# HVDCS_S3A6_48_TQFP_v1p00.net
KiCad netlist of a schematic drawn in EAGLE
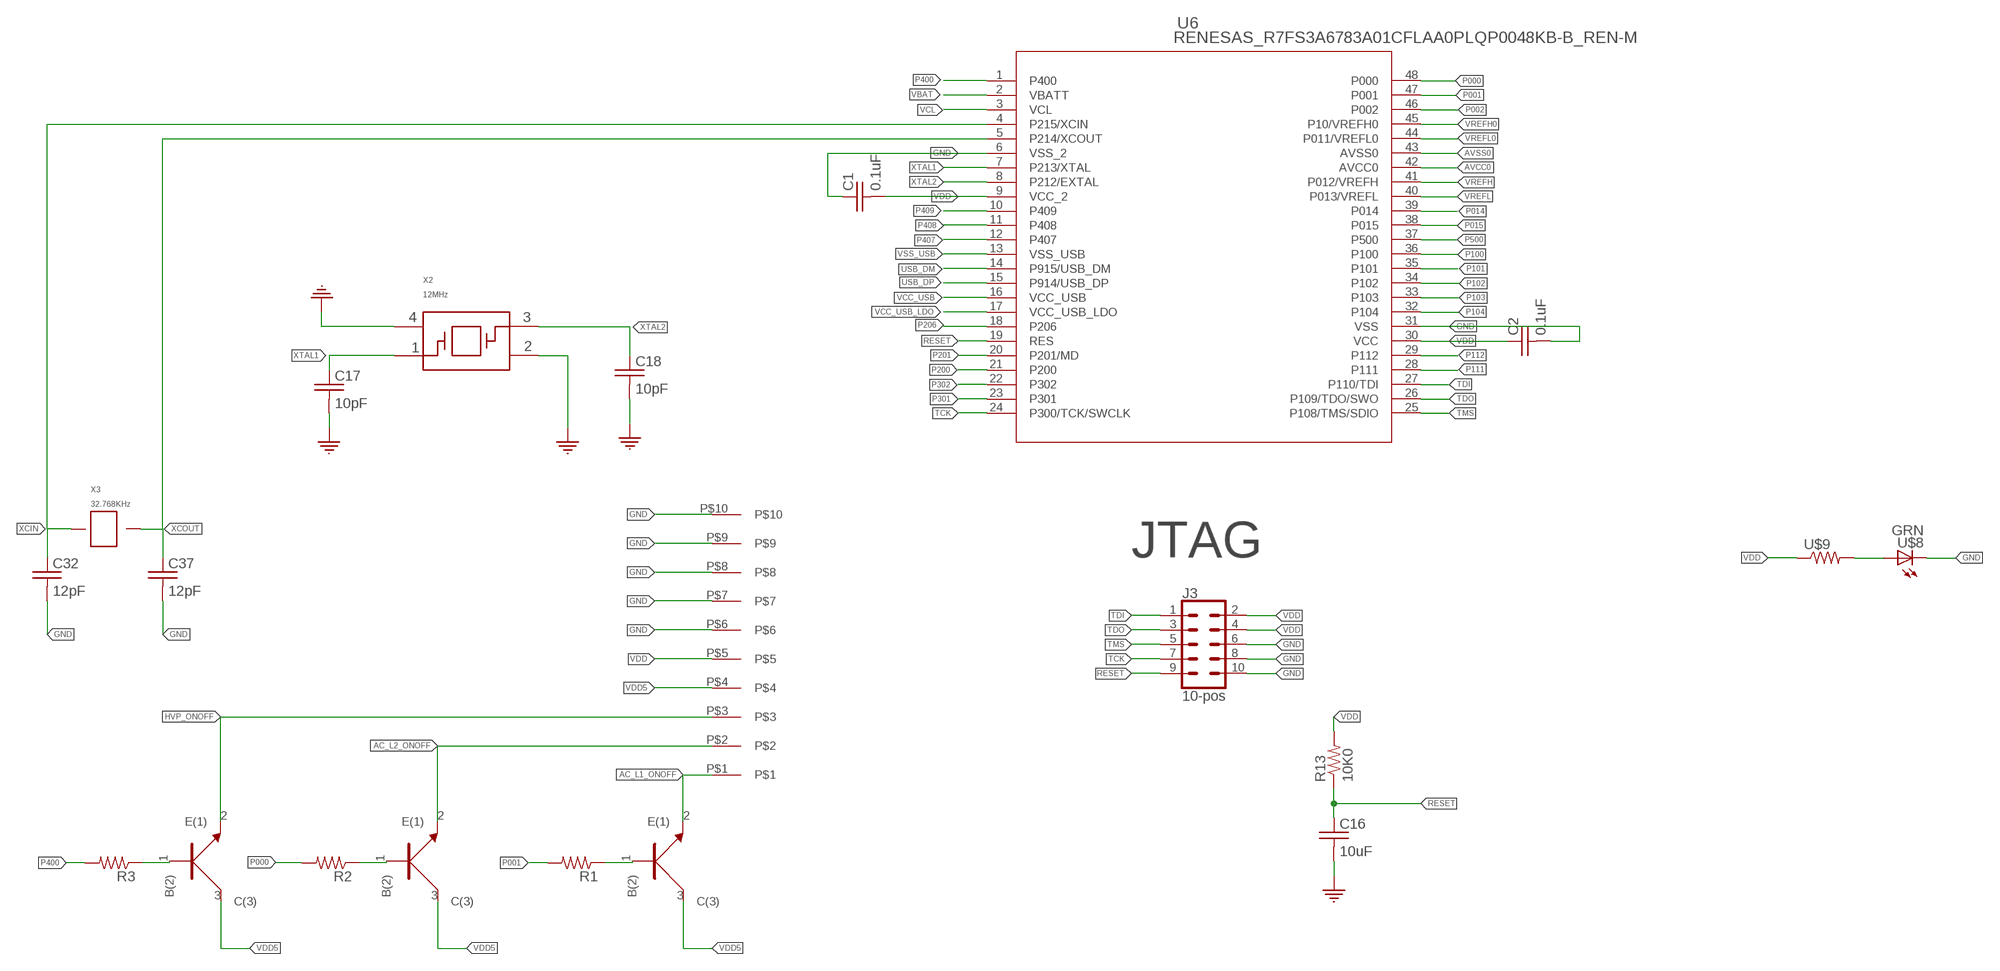
[diagram p0: schematic, sheet 1]

(export (version "E")
  (design (tool "Eeschema 10.0.6"))
  (components
    (comp (ref "C1")
      (value "0.1uF")
      (footprint "eagle-import:0402")
      (fields (field (name "PARTNO") "CL05F104ZO5NNNC"))
      (libsource (lib "eagle-import") (part "C_0402_0.1UF"))
    )
    (comp (ref "C2")
      (value "0.1uF")
      (footprint "eagle-import:0402")
      (fields (field (name "PARTNO") "CL05F104ZO5NNNC"))
      (libsource (lib "eagle-import") (part "C_0402_0.1UF"))
    )
    (comp (ref "C16")
      (value "10uF")
      (footprint "eagle-import:0402")
      (fields (field (name "PARTNO") "CL05A106MP8NUB8"))
      (libsource (lib "eagle-import") (part "C_0402_10UF"))
    )
    (comp (ref "C17")
      (value "10pF")
      (footprint "eagle-import:0402")
      (fields (field (name "PARTNO") "UMK105CG180JV-F"))
      (libsource (lib "eagle-import") (part "C_0402_18PF"))
    )
    (comp (ref "C18")
      (value "10pF")
      (footprint "eagle-import:0402")
      (fields (field (name "PARTNO") "UMK105CG180JV-F"))
      (libsource (lib "eagle-import") (part "C_0402_18PF"))
    )
    (comp (ref "C32")
      (value "12pF")
      (footprint "eagle-import:0402")
      (fields (field (name "PARTNO") "CL05C120JB5NNNC"))
      (libsource (lib "eagle-import") (part "C_0402_12PF"))
    )
    (comp (ref "C37")
      (value "12pF")
      (footprint "eagle-import:0402")
      (fields (field (name "PARTNO") "CL05C120JB5NNNC"))
      (libsource (lib "eagle-import") (part "C_0402_12PF"))
    )
    (comp (ref "J3")
      (value "10-pos")
      (footprint "eagle-import:2X5")
      (fields (field (name "PARTNO") "PH2RA-10-UA"))
      (libsource (lib "eagle-import") (part "CONN_05X2_RAPTH"))
    )
    (comp (ref "R1")
      (value "R_0402")
      (footprint "eagle-import:0402")
      (libsource (lib "eagle-import") (part "R_0402"))
    )
    (comp (ref "R2")
      (value "R_0402")
      (footprint "eagle-import:0402")
      (libsource (lib "eagle-import") (part "R_0402"))
    )
    (comp (ref "R3")
      (value "R_0402")
      (footprint "eagle-import:0402")
      (libsource (lib "eagle-import") (part "R_0402"))
    )
    (comp (ref "R13")
      (value "10K0")
      (footprint "eagle-import:0402")
      (fields (field (name "PARTNO") "RMCF0402JT10K0"))
      (libsource (lib "eagle-import") (part "R_0402_10K0"))
    )
    (comp (ref "U$5")
      (value "1_X_10_HEADER_GENERIC_.1INCH")
      (footprint "eagle-import:HEADER_1_X_10_.1_INCH")
      (libsource (lib "eagle-import") (part "1_X_10_HEADER_GENERIC_.1INCH"))
    )
    (comp (ref "U$8")
      (value "LED_0805_GREEN")
      (footprint "eagle-import:LED_0805_GREEN")
      (libsource (lib "eagle-import") (part "LED_0805_GREEN"))
    )
    (comp (ref "U$9")
      (value "470R0")
      (footprint "eagle-import:0402")
      (fields (field (name "PARTNO") "RMCF0402JT470R"))
      (libsource (lib "eagle-import") (part "R_0402_470R0"))
    )
    (comp (ref "U1")
      (value "NPN")
      (footprint "eagle-import:SOT323")
      (fields (field (name "PARTNO") "BC846BW_NPN"))
      (libsource (lib "eagle-import") (part "BC846BW"))
    )
    (comp (ref "U2")
      (value "NPN")
      (footprint "eagle-import:SOT323")
      (fields (field (name "PARTNO") "BC846BW_NPN"))
      (libsource (lib "eagle-import") (part "BC846BW"))
    )
    (comp (ref "U3")
      (value "NPN")
      (footprint "eagle-import:SOT323")
      (fields (field (name "PARTNO") "BC846BW_NPN"))
      (libsource (lib "eagle-import") (part "BC846BW"))
    )
    (comp (ref "U6")
      (value "RENESAS_R7FS3A6783A01CFLAA0PLQP0048KB-B_REN-M")
      (footprint "eagle-import:PLQP0048KB-B_REN-M")
      (fields
        (field (name "MANUFACTURER_PART_NUMBER") "R7FS3A6783A01CFL#AA0")
        (field (name "COPYRIGHT") "Copyright (C) 2021 Accelerated Designs. All rights reserved")
      )
      (libsource (lib "eagle-import") (part "RENESAS_R7FS3A6783A01CFLAA0PLQP0048KB-B_REN-M"))
    )
    (comp (ref "X2")
      (value "12MHz")
      (footprint "eagle-import:SMD_3225")
      (fields (field (name "PARTNO") "FA-238 24.0000MB-C3 "))
      (libsource (lib "eagle-import") (part "XTAL_24_MHZ"))
    )
    (comp (ref "X3")
      (value "32.768KHz")
      (footprint "eagle-import:SMD_X_2_PADS")
      (fields (field (name "PARTNO") "ABS07-32.768KHZ-T"))
      (libsource (lib "eagle-import") (part "XTAL_32.768KHZ"))
    )
  )
  (nets
    (net (code "1") (name "AC_L1_ONOFF") (class "Default")
      (node (ref "U$5") (pin "P$1") (pinfunction "P$1_P$1") (pintype "bidirectional"))
      (node (ref "U1") (pin "2") (pinfunction "E(1)_2") (pintype "output"))
    )
    (net (code "2") (name "AC_L2_ONOFF") (class "Default")
      (node (ref "U$5") (pin "P$2") (pinfunction "P$2_P$2") (pintype "bidirectional"))
      (node (ref "U2") (pin "2") (pinfunction "E(1)_2") (pintype "output"))
    )
    (net (code "3") (name "AVCC0") (class "Default")
      (node (ref "U6") (pin "42") (pinfunction "AVCC0_42") (pintype "power_in"))
    )
    (net (code "4") (name "AVSS0") (class "Default")
      (node (ref "U6") (pin "43") (pinfunction "AVSS0_43") (pintype "passive"))
    )
    (net (code "5") (name "GND") (class "Default")
      (node (ref "C1") (pin "P$1") (pinfunction "1_P$1") (pintype "passive"))
      (node (ref "C16") (pin "P$2") (pinfunction "2_P$2") (pintype "passive"))
      (node (ref "C17") (pin "P$2") (pinfunction "2_P$2") (pintype "passive"))
      (node (ref "C18") (pin "P$2") (pinfunction "2_P$2") (pintype "passive"))
      (node (ref "C2") (pin "P$2") (pinfunction "2_P$2") (pintype "passive"))
      (node (ref "C32") (pin "P$2") (pinfunction "2_P$2") (pintype "passive"))
      (node (ref "C37") (pin "P$2") (pinfunction "2_P$2") (pintype "passive"))
      (node (ref "J3") (pin "10") (pinfunction "10_10") (pintype "passive"))
      (node (ref "J3") (pin "6") (pinfunction "6_6") (pintype "passive"))
      (node (ref "J3") (pin "8") (pinfunction "8_8") (pintype "passive"))
      (node (ref "U$5") (pin "P$10") (pinfunction "P$10_P$10") (pintype "bidirectional"))
      (node (ref "U$5") (pin "P$6") (pinfunction "P$6_P$6") (pintype "bidirectional"))
      (node (ref "U$5") (pin "P$7") (pinfunction "P$7_P$7") (pintype "bidirectional"))
      (node (ref "U$5") (pin "P$8") (pinfunction "P$8_P$8") (pintype "bidirectional"))
      (node (ref "U$5") (pin "P$9") (pinfunction "P$9_P$9") (pintype "bidirectional"))
      (node (ref "U$8") (pin "C") (pinfunction "C_C") (pintype "passive"))
      (node (ref "U6") (pin "31") (pinfunction "VSS_31") (pintype "passive"))
      (node (ref "U6") (pin "6") (pinfunction "VSS_2_6") (pintype "passive"))
      (node (ref "X2") (pin "2") (pinfunction "2_2") (pintype "bidirectional"))
      (node (ref "X2") (pin "4") (pinfunction "4_4") (pintype "bidirectional"))
    )
    (net (code "6") (name "HVP_ONOFF") (class "Default")
      (node (ref "U$5") (pin "P$3") (pinfunction "P$3_P$3") (pintype "bidirectional"))
      (node (ref "U3") (pin "2") (pinfunction "E(1)_2") (pintype "output"))
    )
    (net (code "7") (name "Net-(R1-1)") (class "Default")
      (node (ref "R1") (pin "P$1") (pinfunction "1_P$1") (pintype "passive"))
      (node (ref "U1") (pin "1") (pinfunction "B(2)_1") (pintype "input"))
    )
    (net (code "8") (name "Net-(R2-1)") (class "Default")
      (node (ref "R2") (pin "P$1") (pinfunction "1_P$1") (pintype "passive"))
      (node (ref "U2") (pin "1") (pinfunction "B(2)_1") (pintype "input"))
    )
    (net (code "9") (name "Net-(R3-1)") (class "Default")
      (node (ref "R3") (pin "P$1") (pinfunction "1_P$1") (pintype "passive"))
      (node (ref "U3") (pin "1") (pinfunction "B(2)_1") (pintype "input"))
    )
    (net (code "10") (name "Net-(U$9-2)") (class "Default")
      (node (ref "U$8") (pin "A") (pinfunction "A_A") (pintype "passive"))
      (node (ref "U$9") (pin "P$2") (pinfunction "2_P$2") (pintype "passive"))
    )
    (net (code "11") (name "P000") (class "Default")
      (node (ref "R2") (pin "P$2") (pinfunction "2_P$2") (pintype "passive"))
      (node (ref "U6") (pin "48") (pinfunction "P000_48") (pintype "bidirectional"))
    )
    (net (code "12") (name "P001") (class "Default")
      (node (ref "R1") (pin "P$2") (pinfunction "2_P$2") (pintype "passive"))
      (node (ref "U6") (pin "47") (pinfunction "P001_47") (pintype "bidirectional"))
    )
    (net (code "13") (name "P002") (class "Default")
      (node (ref "U6") (pin "46") (pinfunction "P002_46") (pintype "bidirectional"))
    )
    (net (code "14") (name "P014") (class "Default")
      (node (ref "U6") (pin "39") (pinfunction "P014_39") (pintype "bidirectional"))
    )
    (net (code "15") (name "P015") (class "Default")
      (node (ref "U6") (pin "38") (pinfunction "P015_38") (pintype "bidirectional"))
    )
    (net (code "16") (name "P100") (class "Default")
      (node (ref "U6") (pin "36") (pinfunction "P100_36") (pintype "bidirectional"))
    )
    (net (code "17") (name "P101") (class "Default")
      (node (ref "U6") (pin "35") (pinfunction "P101_35") (pintype "bidirectional"))
    )
    (net (code "18") (name "P102") (class "Default")
      (node (ref "U6") (pin "34") (pinfunction "P102_34") (pintype "bidirectional"))
    )
    (net (code "19") (name "P103") (class "Default")
      (node (ref "U6") (pin "33") (pinfunction "P103_33") (pintype "bidirectional"))
    )
    (net (code "20") (name "P104") (class "Default")
      (node (ref "U6") (pin "32") (pinfunction "P104_32") (pintype "bidirectional"))
    )
    (net (code "21") (name "P111") (class "Default")
      (node (ref "U6") (pin "28") (pinfunction "P111_28") (pintype "bidirectional"))
    )
    (net (code "22") (name "P112") (class "Default")
      (node (ref "U6") (pin "29") (pinfunction "P112_29") (pintype "bidirectional"))
    )
    (net (code "23") (name "P200") (class "Default")
      (node (ref "U6") (pin "21") (pinfunction "P200_21") (pintype "bidirectional"))
    )
    (net (code "24") (name "P201") (class "Default")
      (node (ref "U6") (pin "20") (pinfunction "P201/MD_20") (pintype "bidirectional"))
    )
    (net (code "25") (name "P206") (class "Default")
      (node (ref "U6") (pin "18") (pinfunction "P206_18") (pintype "bidirectional"))
    )
    (net (code "26") (name "P301") (class "Default")
      (node (ref "U6") (pin "23") (pinfunction "P301_23") (pintype "bidirectional"))
    )
    (net (code "27") (name "P302") (class "Default")
      (node (ref "U6") (pin "22") (pinfunction "P302_22") (pintype "bidirectional"))
    )
    (net (code "28") (name "P400") (class "Default")
      (node (ref "R3") (pin "P$2") (pinfunction "2_P$2") (pintype "passive"))
      (node (ref "U6") (pin "1") (pinfunction "P400_1") (pintype "bidirectional"))
    )
    (net (code "29") (name "P407") (class "Default")
      (node (ref "U6") (pin "12") (pinfunction "P407_12") (pintype "bidirectional"))
    )
    (net (code "30") (name "P408") (class "Default")
      (node (ref "U6") (pin "11") (pinfunction "P408_11") (pintype "bidirectional"))
    )
    (net (code "31") (name "P409") (class "Default")
      (node (ref "U6") (pin "10") (pinfunction "P409_10") (pintype "bidirectional"))
    )
    (net (code "32") (name "P500") (class "Default")
      (node (ref "U6") (pin "37") (pinfunction "P500_37") (pintype "bidirectional"))
    )
    (net (code "33") (name "RESET") (class "Default")
      (node (ref "C16") (pin "P$1") (pinfunction "1_P$1") (pintype "passive"))
      (node (ref "J3") (pin "9") (pinfunction "9_9") (pintype "passive"))
      (node (ref "R13") (pin "P$1") (pinfunction "1_P$1") (pintype "passive"))
      (node (ref "U6") (pin "19") (pinfunction "RES_19") (pintype "passive"))
    )
    (net (code "34") (name "TCK") (class "Default")
      (node (ref "J3") (pin "7") (pinfunction "7_7") (pintype "passive"))
      (node (ref "U6") (pin "24") (pinfunction "P300/TCK/SWCLK_24") (pintype "bidirectional"))
    )
    (net (code "35") (name "TDI") (class "Default")
      (node (ref "J3") (pin "1") (pinfunction "1_1") (pintype "passive"))
      (node (ref "U6") (pin "27") (pinfunction "P110/TDI_27") (pintype "bidirectional"))
    )
    (net (code "36") (name "TDO") (class "Default")
      (node (ref "J3") (pin "3") (pinfunction "3_3") (pintype "passive"))
      (node (ref "U6") (pin "26") (pinfunction "P109/TDO/SWO_26") (pintype "bidirectional"))
    )
    (net (code "37") (name "TMS") (class "Default")
      (node (ref "J3") (pin "5") (pinfunction "5_5") (pintype "passive"))
      (node (ref "U6") (pin "25") (pinfunction "P108/TMS/SDIO_25") (pintype "bidirectional"))
    )
    (net (code "38") (name "USB_DM") (class "Default")
      (node (ref "U6") (pin "14") (pinfunction "P915/USB_DM_14") (pintype "bidirectional"))
    )
    (net (code "39") (name "USB_DP") (class "Default")
      (node (ref "U6") (pin "15") (pinfunction "P914/USB_DP_15") (pintype "bidirectional"))
    )
    (net (code "40") (name "VBAT") (class "Default")
      (node (ref "U6") (pin "2") (pinfunction "VBATT_2") (pintype "passive"))
    )
    (net (code "41") (name "VCC_USB") (class "Default")
      (node (ref "U6") (pin "16") (pinfunction "VCC_USB_16") (pintype "power_in"))
    )
    (net (code "42") (name "VCC_USB_LDO") (class "Default")
      (node (ref "U6") (pin "17") (pinfunction "VCC_USB_LDO_17") (pintype "power_in"))
    )
    (net (code "43") (name "VCL") (class "Default")
      (node (ref "U6") (pin "3") (pinfunction "VCL_3") (pintype "passive"))
    )
    (net (code "44") (name "VDD") (class "Default")
      (node (ref "C1") (pin "P$2") (pinfunction "2_P$2") (pintype "passive"))
      (node (ref "C2") (pin "P$1") (pinfunction "1_P$1") (pintype "passive"))
      (node (ref "J3") (pin "2") (pinfunction "2_2") (pintype "passive"))
      (node (ref "J3") (pin "4") (pinfunction "4_4") (pintype "passive"))
      (node (ref "R13") (pin "P$2") (pinfunction "2_P$2") (pintype "passive"))
      (node (ref "U$5") (pin "P$5") (pinfunction "P$5_P$5") (pintype "bidirectional"))
      (node (ref "U$9") (pin "P$1") (pinfunction "1_P$1") (pintype "passive"))
      (node (ref "U6") (pin "30") (pinfunction "VCC_30") (pintype "power_in"))
      (node (ref "U6") (pin "9") (pinfunction "VCC_2_9") (pintype "power_in"))
    )
    (net (code "45") (name "VDD5") (class "Default")
      (node (ref "U$5") (pin "P$4") (pinfunction "P$4_P$4") (pintype "bidirectional"))
      (node (ref "U1") (pin "3") (pinfunction "C(3)_3") (pintype "input"))
      (node (ref "U2") (pin "3") (pinfunction "C(3)_3") (pintype "input"))
      (node (ref "U3") (pin "3") (pinfunction "C(3)_3") (pintype "input"))
    )
    (net (code "46") (name "VREFH") (class "Default")
      (node (ref "U6") (pin "41") (pinfunction "P012/VREFH_41") (pintype "power_in"))
    )
    (net (code "47") (name "VREFH0") (class "Default")
      (node (ref "U6") (pin "45") (pinfunction "P10/VREFH0_45") (pintype "power_in"))
    )
    (net (code "48") (name "VREFL") (class "Default")
      (node (ref "U6") (pin "40") (pinfunction "P013/VREFL_40") (pintype "power_in"))
    )
    (net (code "49") (name "VREFL0") (class "Default")
      (node (ref "U6") (pin "44") (pinfunction "P011/VREFL0_44") (pintype "power_in"))
    )
    (net (code "50") (name "VSS_USB") (class "Default")
      (node (ref "U6") (pin "13") (pinfunction "VSS_USB_13") (pintype "passive"))
    )
    (net (code "51") (name "XCIN") (class "Default")
      (node (ref "C32") (pin "P$1") (pinfunction "1_P$1") (pintype "passive"))
      (node (ref "U6") (pin "4") (pinfunction "P215/XCIN_4") (pintype "bidirectional"))
      (node (ref "X3") (pin "P$1") (pinfunction "P$1_P$1") (pintype "bidirectional"))
    )
    (net (code "52") (name "XCOUT") (class "Default")
      (node (ref "C37") (pin "P$1") (pinfunction "1_P$1") (pintype "passive"))
      (node (ref "U6") (pin "5") (pinfunction "P214/XCOUT_5") (pintype "output"))
      (node (ref "X3") (pin "P$2") (pinfunction "P$2_P$2") (pintype "bidirectional"))
    )
    (net (code "53") (name "XTAL1") (class "Default")
      (node (ref "C17") (pin "P$1") (pinfunction "1_P$1") (pintype "passive"))
      (node (ref "U6") (pin "7") (pinfunction "P213/XTAL_7") (pintype "bidirectional"))
      (node (ref "X2") (pin "1") (pinfunction "1_1") (pintype "bidirectional"))
    )
    (net (code "54") (name "XTAL2") (class "Default")
      (node (ref "C18") (pin "P$1") (pinfunction "1_P$1") (pintype "passive"))
      (node (ref "U6") (pin "8") (pinfunction "P212/EXTAL_8") (pintype "bidirectional"))
      (node (ref "X2") (pin "3") (pinfunction "3_3") (pintype "bidirectional"))
    )
  )
)
